# buck-converter.net
KiCad netlist of a schematic drawn in EAGLE
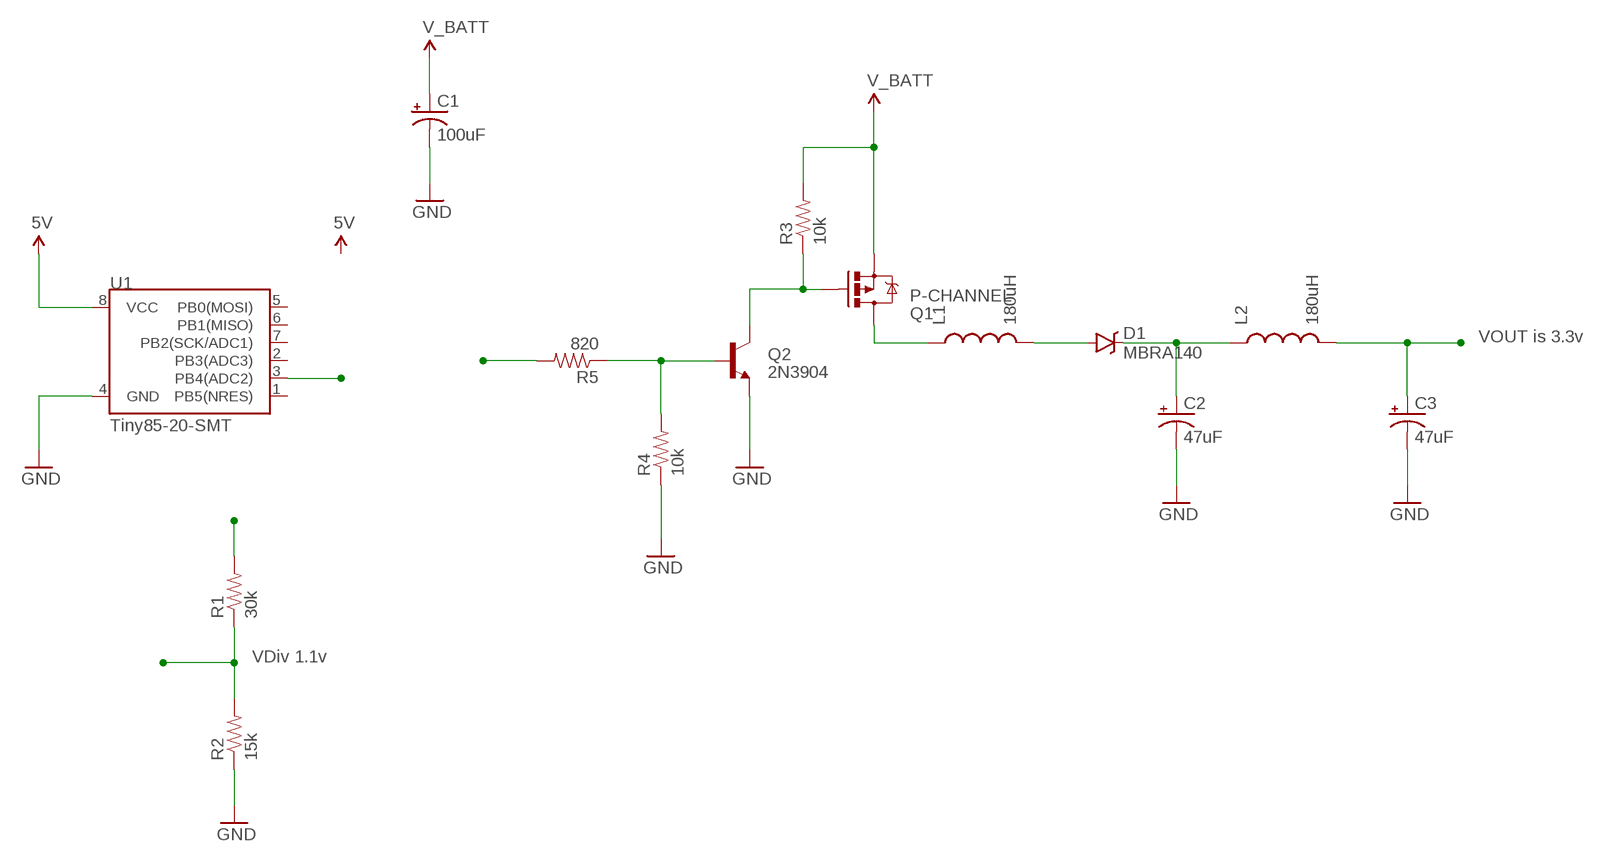
[diagram p0: schematic, sheet 1]

(export (version "E")
  (design (tool "Eeschema 10.0.6"))
  (components
    (comp (ref "C1")
      (value "100uF")
      (footprint "eagle-import:PANASONIC_D")
      (libsource (lib "eagle-import") (part "47UF-50V-20%(ELECT)"))
    )
    (comp (ref "C2")
      (value "47uF")
      (footprint "eagle-import:PANASONIC_D")
      (libsource (lib "eagle-import") (part "47UF-50V-20%(ELECT)"))
    )
    (comp (ref "C3")
      (value "47uF")
      (footprint "eagle-import:PANASONIC_D")
      (libsource (lib "eagle-import") (part "47UF-50V-20%(ELECT)"))
    )
    (comp (ref "D1")
      (value "MBRA140")
      (footprint "eagle-import:SMA-DIODE")
      (libsource (lib "eagle-import") (part "DIODE-SCHOTTKY-MBRA140"))
    )
    (comp (ref "L1")
      (value "180uH")
      (footprint "eagle-import:CR54")
      (libsource (lib "eagle-import") (part "INDUCTORCR54"))
    )
    (comp (ref "L2")
      (value "180uH")
      (footprint "eagle-import:CR54")
      (libsource (lib "eagle-import") (part "INDUCTORCR54"))
    )
    (comp (ref "Q1")
      (value "P-CHANNEL")
      (footprint "eagle-import:SOT23-3")
      (libsource (lib "eagle-import") (part "MOSFET-PCHANNELSMD"))
    )
    (comp (ref "Q2")
      (value "2N3904")
      (footprint "eagle-import:TO-92-AMMO")
      (libsource (lib "eagle-import") (part "TRANSISTOR_NPNBC547"))
    )
    (comp (ref "R1")
      (value "30k")
      (footprint "eagle-import:0603-RES")
      (libsource (lib "eagle-import") (part "RESISTOR0603"))
    )
    (comp (ref "R2")
      (value "15k")
      (footprint "eagle-import:0603-RES")
      (libsource (lib "eagle-import") (part "RESISTOR0603"))
    )
    (comp (ref "R3")
      (value "10k")
      (footprint "eagle-import:0603-RES")
      (libsource (lib "eagle-import") (part "RESISTOR0603"))
    )
    (comp (ref "R4")
      (value "10k")
      (footprint "eagle-import:0603-RES")
      (libsource (lib "eagle-import") (part "RESISTOR0603"))
    )
    (comp (ref "R5")
      (value "820")
      (footprint "eagle-import:0603-RES")
      (libsource (lib "eagle-import") (part "RESISTOR0603"))
    )
    (comp (ref "U1")
      (value "Tiny85-20-SMT")
      (footprint "eagle-import:SO08-EIAJ")
      (libsource (lib "eagle-import") (part "ATTINY45TINY85-20-SMT"))
    )
  )
  (nets
    (net (code "1") (name "/PWM") (class "Default")
      (node (ref "R5") (pin "2") (pinfunction "2_2") (pintype "passive"))
      (node (ref "U1") (pin "3") (pinfunction "PB4(ADC2)_3") (pintype "bidirectional"))
    )
    (net (code "2") (name "/VOUT") (class "Default")
      (node (ref "C3") (pin "+") (pinfunction "+_+") (pintype "passive"))
      (node (ref "L2") (pin "P$2") (pinfunction "2_P$2") (pintype "passive"))
      (node (ref "R1") (pin "2") (pinfunction "2_2") (pintype "passive"))
    )
    (net (code "3") (name "5V") (class "Default")
      (node (ref "U1") (pin "8") (pinfunction "VCC_8") (pintype "bidirectional"))
    )
    (net (code "4") (name "GND") (class "Default")
      (node (ref "C1") (pin "-") (pinfunction "-_-") (pintype "passive"))
      (node (ref "C2") (pin "-") (pinfunction "-_-") (pintype "passive"))
      (node (ref "C3") (pin "-") (pinfunction "-_-") (pintype "passive"))
      (node (ref "Q2") (pin "3") (pinfunction "E_3") (pintype "passive"))
      (node (ref "R2") (pin "1") (pinfunction "1_1") (pintype "passive"))
      (node (ref "R4") (pin "1") (pinfunction "1_1") (pintype "passive"))
      (node (ref "U1") (pin "4") (pinfunction "GND_4") (pintype "bidirectional"))
    )
    (net (code "5") (name "Net-(L1-1)") (class "Default")
      (node (ref "L1") (pin "P$1") (pinfunction "1_P$1") (pintype "passive"))
      (node (ref "Q1") (pin "3") (pinfunction "D_3") (pintype "passive"))
    )
    (net (code "6") (name "Net-(L1-2)") (class "Default")
      (node (ref "D1") (pin "A") (pinfunction "A_A") (pintype "passive"))
      (node (ref "L1") (pin "P$2") (pinfunction "2_P$2") (pintype "passive"))
    )
    (net (code "7") (name "Net-(L2-1)") (class "Default")
      (node (ref "C2") (pin "+") (pinfunction "+_+") (pintype "passive"))
      (node (ref "D1") (pin "C") (pinfunction "C_C") (pintype "passive"))
      (node (ref "L2") (pin "P$1") (pinfunction "1_P$1") (pintype "passive"))
    )
    (net (code "8") (name "Net-(Q1-G)") (class "Default")
      (node (ref "Q1") (pin "1") (pinfunction "G_1") (pintype "passive"))
      (node (ref "Q2") (pin "1") (pinfunction "C_1") (pintype "passive"))
      (node (ref "R3") (pin "1") (pinfunction "1_1") (pintype "passive"))
    )
    (net (code "9") (name "Net-(Q2-B)") (class "Default")
      (node (ref "Q2") (pin "2") (pinfunction "B_2") (pintype "passive"))
      (node (ref "R4") (pin "2") (pinfunction "2_2") (pintype "passive"))
      (node (ref "R5") (pin "1") (pinfunction "1_1") (pintype "passive"))
    )
    (net (code "10") (name "Net-(R1-Pad1)") (class "Default")
      (node (ref "R1") (pin "1") (pinfunction "1_1") (pintype "passive"))
      (node (ref "R2") (pin "2") (pinfunction "2_2") (pintype "passive"))
    )
    (net (code "11") (name "V_BATT") (class "Default")
      (node (ref "C1") (pin "+") (pinfunction "+_+") (pintype "passive"))
      (node (ref "Q1") (pin "2") (pinfunction "S_2") (pintype "passive"))
      (node (ref "R3") (pin "2") (pinfunction "2_2") (pintype "passive"))
    )
    (net (code "12") (name "unconnected-(U1-PB0(MOSI)-Pad5)") (class "Default")
      (node (ref "U1") (pin "5") (pinfunction "PB0(MOSI)_5") (pintype "bidirectional"))
    )
    (net (code "13") (name "unconnected-(U1-PB1(MISO)-Pad6)") (class "Default")
      (node (ref "U1") (pin "6") (pinfunction "PB1(MISO)_6") (pintype "bidirectional"))
    )
    (net (code "14") (name "unconnected-(U1-PB2(SCK{slash}ADC1)-Pad7)") (class "Default")
      (node (ref "U1") (pin "7") (pinfunction "PB2(SCK/ADC1)_7") (pintype "bidirectional"))
    )
    (net (code "15") (name "unconnected-(U1-PB3(ADC3)-Pad2)") (class "Default")
      (node (ref "U1") (pin "2") (pinfunction "PB3(ADC3)_2") (pintype "bidirectional"))
    )
    (net (code "16") (name "unconnected-(U1-PB5(NRES)-Pad1)") (class "Default")
      (node (ref "U1") (pin "1") (pinfunction "PB5(NRES)_1") (pintype "bidirectional"))
    )
  )
)
